# USB_Hub.net
KiCad netlist of a schematic drawn in Altium Designer
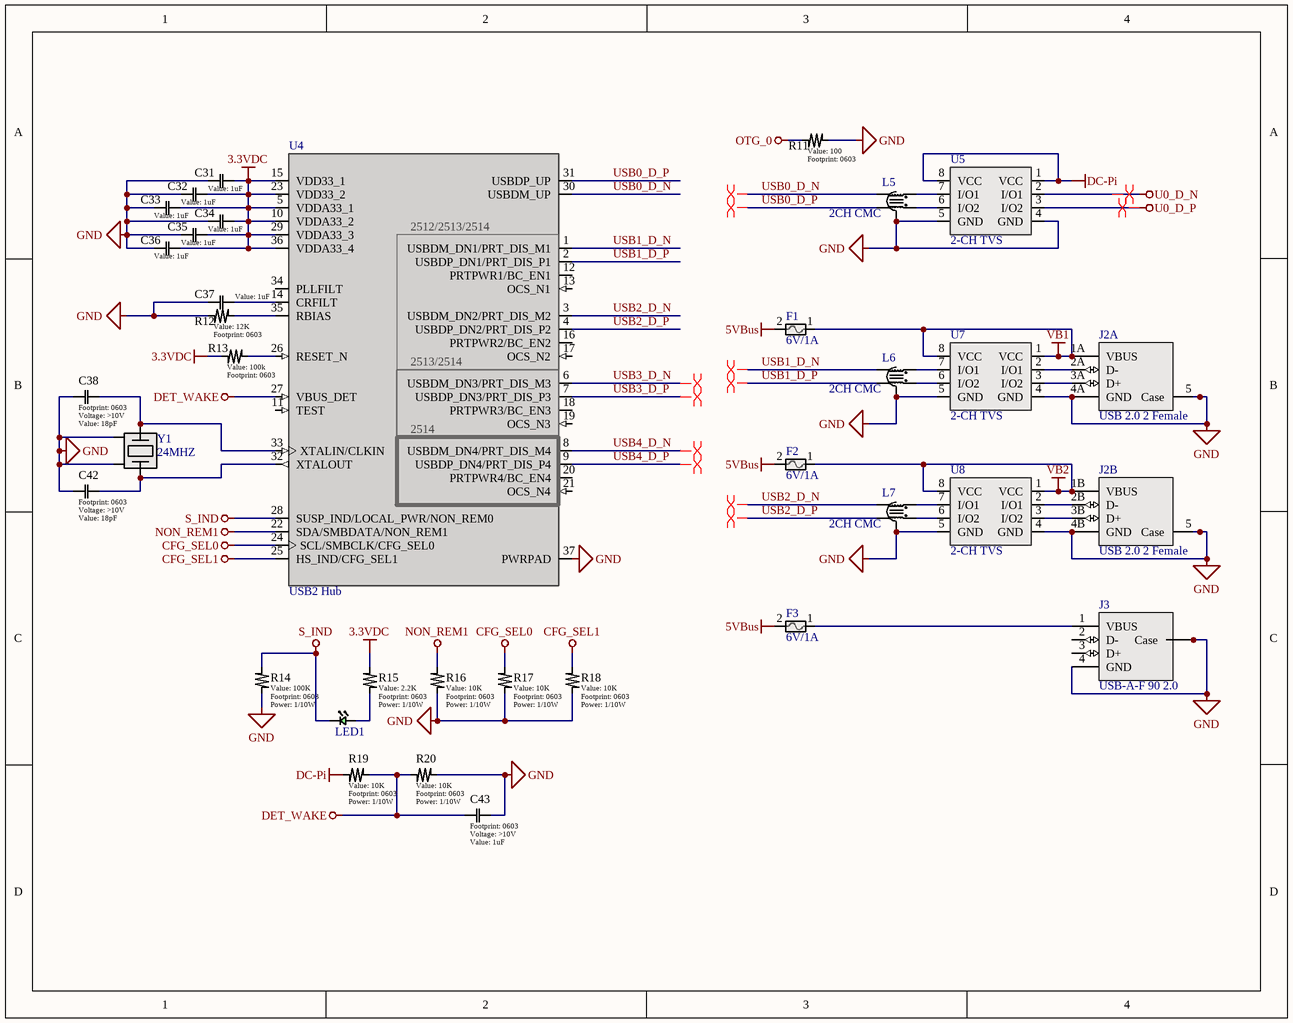
[diagram p0: USB Hub.SchDoc]

(export (version "E")
  (design (tool "Eeschema 10.0.6"))
  (components
    (comp (ref "C31")
      (value "1uF")
      (footprint "0603")
      (fields
        (field (name "VOLTAGE") ">10V")
        (field (name "TOLERANCE") "10%")
        (field (name "Comment") "Generic Capacitor")
      )
      (libsource (lib "Capacitors") (part "Generic Capacitor"))
    )
    (comp (ref "C32")
      (value "1uF")
      (footprint "0603")
      (fields
        (field (name "VOLTAGE") ">10V")
        (field (name "TOLERANCE") "10%")
        (field (name "Comment") "Generic Capacitor")
      )
      (libsource (lib "Capacitors") (part "Generic Capacitor"))
    )
    (comp (ref "C33")
      (value "1uF")
      (footprint "0603")
      (fields
        (field (name "VOLTAGE") ">10V")
        (field (name "TOLERANCE") "10%")
        (field (name "Comment") "Generic Capacitor")
      )
      (libsource (lib "Capacitors") (part "Generic Capacitor"))
    )
    (comp (ref "C34")
      (value "1uF")
      (footprint "0603")
      (fields
        (field (name "VOLTAGE") ">10V")
        (field (name "TOLERANCE") "10%")
        (field (name "Comment") "Generic Capacitor")
      )
      (libsource (lib "Capacitors") (part "Generic Capacitor"))
    )
    (comp (ref "C35")
      (value "1uF")
      (footprint "0603")
      (fields
        (field (name "VOLTAGE") ">10V")
        (field (name "TOLERANCE") "10%")
        (field (name "Comment") "Generic Capacitor")
      )
      (libsource (lib "Capacitors") (part "Generic Capacitor"))
    )
    (comp (ref "C36")
      (value "1uF")
      (footprint "0603")
      (fields
        (field (name "VOLTAGE") ">10V")
        (field (name "TOLERANCE") "10%")
        (field (name "Comment") "Generic Capacitor")
      )
      (libsource (lib "Capacitors") (part "Generic Capacitor"))
    )
    (comp (ref "C37")
      (value "1uF")
      (footprint "0603")
      (fields
        (field (name "VOLTAGE") ">10V")
        (field (name "TOLERANCE") "10%")
        (field (name "Comment") "Generic Capacitor")
      )
      (libsource (lib "Capacitors") (part "Generic Capacitor"))
    )
    (comp (ref "C38")
      (value "18pF")
      (footprint "0603")
      (fields
        (field (name "VOLTAGE") ">10V")
        (field (name "TOLERANCE") "10%")
        (field (name "Comment") "Generic Capacitor")
      )
      (libsource (lib "Capacitors") (part "Generic Capacitor"))
    )
    (comp (ref "C42")
      (value "18pF")
      (footprint "0603")
      (fields
        (field (name "VOLTAGE") ">10V")
        (field (name "TOLERANCE") "10%")
        (field (name "Comment") "Generic Capacitor")
      )
      (libsource (lib "Capacitors") (part "Generic Capacitor"))
    )
    (comp (ref "C43")
      (value "1uF")
      (footprint "0603")
      (fields
        (field (name "VOLTAGE") ">10V")
        (field (name "TOLERANCE") "10%")
        (field (name "Comment") "Generic Capacitor")
      )
      (libsource (lib "Capacitors") (part "Generic Capacitor"))
    )
    (comp (ref "F1")
      (value "6V/1A")
      (footprint "0805")
      (description "Polymeric PTC Resettable Fuse 6V 1 A Ih Surface Mount 0805 (2012 Metric), Concave")
      (fields (field (name "MANUFACTURER") "Bel") (field (name "MANUFACTURER PART NUMBER") "0ZCK0100FF2E"))
      (libsource (lib "Regulators") (part "0ZCK0100FF2E"))
    )
    (comp (ref "F2")
      (value "6V/1A")
      (footprint "0805")
      (description "Polymeric PTC Resettable Fuse 6V 1 A Ih Surface Mount 0805 (2012 Metric), Concave")
      (fields (field (name "MANUFACTURER") "Bel") (field (name "MANUFACTURER PART NUMBER") "0ZCK0100FF2E"))
      (libsource (lib "Regulators") (part "0ZCK0100FF2E"))
    )
    (comp (ref "F3")
      (value "6V/1A")
      (footprint "0805")
      (description "Polymeric PTC Resettable Fuse 6V 1 A Ih Surface Mount 0805 (2012 Metric), Concave")
      (fields (field (name "MANUFACTURER") "Bel") (field (name "MANUFACTURER PART NUMBER") "0ZCK0100FF2E"))
      (libsource (lib "Regulators") (part "0ZCK0100FF2E"))
    )
    (comp (ref "J2")
      (value "USB 2.0 2 Female")
      (footprint "907-111A1022D10200")
      (description "USB 2.0 2 8 Female Type-A Plugin USB Connectors ROHS")
      (libsource (lib "Connectors") (part "907-111A1022D10200"))
    )
    (comp (ref "J3")
      (value "USB-A-F 90 2.0")
      (footprint "Molex_67329-8000")
      (description "USB 2.0 1 Side insertion 4P Female Type-A Plugin")
      (libsource (lib "Connectors") (part "673298000"))
    )
    (comp (ref "L5")
      (value "2CH CMC")
      (footprint "SMD-6-2CH")
      (description "35Ω@100MHz -40℃~+85℃ 4Ω 5V 2 100mA SMD Common Mode Filters ROHS")
      (libsource (lib "Inductors") (part "ICMEF112P350MFR"))
    )
    (comp (ref "L6")
      (value "2CH CMC")
      (footprint "SMD-6-2CH")
      (description "35Ω@100MHz -40℃~+85℃ 4Ω 5V 2 100mA SMD Common Mode Filters ROHS")
      (libsource (lib "Inductors") (part "ICMEF112P350MFR"))
    )
    (comp (ref "L7")
      (value "2CH CMC")
      (footprint "SMD-6-2CH")
      (description "35Ω@100MHz -40℃~+85℃ 4Ω 5V 2 100mA SMD Common Mode Filters ROHS")
      (libsource (lib "Inductors") (part "ICMEF112P350MFR"))
    )
    (comp (ref "LED1")
      (value "LTST-C191KGKT")
      (footprint "0603 (1608 Metric) Concave")
      (description "LED Uni-Color Green 574nm 2-Pin Chip LED T/R")
      (libsource (lib "Gamber - Johnson LLC") (part "LTST-C191KGKT"))
    )
    (comp (ref "R11")
      (value "100")
      (footprint "0603")
      (fields
        (field (name "TOLERANCE") "1%")
        (field (name "POWER") "1/10W")
        (field (name "Comment") "Generic Resistor")
      )
      (libsource (lib "Resistors") (part "Generic Resistor"))
    )
    (comp (ref "R12")
      (value "12K")
      (footprint "0603")
      (fields
        (field (name "TOLERANCE") "1%")
        (field (name "POWER") "1/10W")
        (field (name "Comment") "Generic Resistor")
      )
      (libsource (lib "Resistors") (part "Generic Resistor"))
    )
    (comp (ref "R13")
      (value "100k")
      (footprint "0603")
      (fields
        (field (name "TOLERANCE") "1%")
        (field (name "POWER") "1/10W")
        (field (name "Comment") "Generic Resistor")
      )
      (libsource (lib "Resistors") (part "Generic Resistor"))
    )
    (comp (ref "R14")
      (value "100K")
      (footprint "0603")
      (fields
        (field (name "TOLERANCE") "1%")
        (field (name "POWER") "1/10W")
        (field (name "Comment") "Generic Resistor")
      )
      (libsource (lib "Resistors") (part "Generic Resistor"))
    )
    (comp (ref "R15")
      (value "2.2K")
      (footprint "0603")
      (fields
        (field (name "TOLERANCE") "1%")
        (field (name "POWER") "1/10W")
        (field (name "Comment") "Generic Resistor")
      )
      (libsource (lib "Resistors") (part "Generic Resistor"))
    )
    (comp (ref "R16")
      (value "10K")
      (footprint "0603")
      (fields
        (field (name "TOLERANCE") "1%")
        (field (name "POWER") "1/10W")
        (field (name "Comment") "Generic Resistor")
      )
      (libsource (lib "Resistors") (part "Generic Resistor"))
    )
    (comp (ref "R17")
      (value "10K")
      (footprint "0603")
      (fields
        (field (name "TOLERANCE") "1%")
        (field (name "POWER") "1/10W")
        (field (name "Comment") "Generic Resistor")
      )
      (libsource (lib "Resistors") (part "Generic Resistor"))
    )
    (comp (ref "R18")
      (value "10K")
      (footprint "0603")
      (fields
        (field (name "TOLERANCE") "1%")
        (field (name "POWER") "1/10W")
        (field (name "Comment") "Generic Resistor")
      )
      (libsource (lib "Resistors") (part "Generic Resistor"))
    )
    (comp (ref "R19")
      (value "10K")
      (footprint "0603")
      (fields
        (field (name "TOLERANCE") "1%")
        (field (name "POWER") "1/10W")
        (field (name "Comment") "Generic Resistor")
      )
      (libsource (lib "Resistors") (part "Generic Resistor"))
    )
    (comp (ref "R20")
      (value "10K")
      (footprint "0603")
      (fields
        (field (name "TOLERANCE") "1%")
        (field (name "POWER") "1/10W")
        (field (name "Comment") "Generic Resistor")
      )
      (libsource (lib "Resistors") (part "Generic Resistor"))
    )
    (comp (ref "U4")
      (value "USB2 Hub")
      (footprint "36-QFN (6x6)")
      (description "USB Hub Controller USB 2.0 USB Interface 36-QFN _6x6_")
      (fields (field (name "MF") "Microchip") (field (name "DIGI-KEY_PART_NUMBER") "USB2514BI-AEZG-ND"))
      (libsource (lib "Hub ICs") (part "USB251xBI-AEZG"))
    )
    (comp (ref "U5")
      (value "2-CH TVS")
      (footprint "8-SOIC")
      (description "TVS DIODE 5.25VWM 8-SOIC")
      (libsource (lib "Diodes") (part "USB6B1RL"))
    )
    (comp (ref "U7")
      (value "2-CH TVS")
      (footprint "8-SOIC")
      (description "TVS DIODE 5.25VWM 8-SOIC")
      (libsource (lib "Diodes") (part "USB6B1RL"))
    )
    (comp (ref "U8")
      (value "2-CH TVS")
      (footprint "8-SOIC")
      (description "TVS DIODE 5.25VWM 8-SOIC")
      (libsource (lib "Diodes") (part "USB6B1RL"))
    )
    (comp (ref "Y1")
      (value "24MHZ")
      (footprint "SMD2520-4P")
      (description "24MHz 20pF ±10ppm ±30ppm SMD-2520-4P Crystals ROHS")
      (libsource (lib "Misc ICs") (part "CM4024M00020001"))
    )
  )
  (nets
    (net (code "1") (name "/USB0_D_N") (class "Default")
      (node (ref "L5") (pin "4") (pinfunction "4_4") (pintype "passive"))
      (node (ref "U4") (pin "30") (pinfunction "USBDM_UP_30") (pintype "bidirectional"))
    )
    (net (code "2") (name "/USB0_D_P") (class "Default")
      (node (ref "L5") (pin "3") (pinfunction "3_3") (pintype "passive"))
      (node (ref "U4") (pin "31") (pinfunction "USBDP_UP_31") (pintype "bidirectional"))
    )
    (net (code "3") (name "/USB1_D_N") (class "Default")
      (node (ref "L6") (pin "4") (pinfunction "4_4") (pintype "passive"))
      (node (ref "U4") (pin "1") (pinfunction "USBDM_DN1/PRT_DIS_M1_1") (pintype "bidirectional"))
    )
    (net (code "4") (name "/USB1_D_P") (class "Default")
      (node (ref "L6") (pin "3") (pinfunction "3_3") (pintype "passive"))
      (node (ref "U4") (pin "2") (pinfunction "USBDP_DN1/PRT_DIS_P1_2") (pintype "bidirectional"))
    )
    (net (code "5") (name "/USB2_D_N") (class "Default")
      (node (ref "L7") (pin "4") (pinfunction "4_4") (pintype "passive"))
      (node (ref "U4") (pin "3") (pinfunction "USBDM_DN2/PRT_DIS_M2_3") (pintype "bidirectional"))
    )
    (net (code "6") (name "/USB2_D_P") (class "Default")
      (node (ref "L7") (pin "3") (pinfunction "3_3") (pintype "passive"))
      (node (ref "U4") (pin "4") (pinfunction "USBDP_DN2/PRT_DIS_P2_4") (pintype "bidirectional"))
    )
    (net (code "7") (name "/USB3_D_N") (class "Default")
      (node (ref "U4") (pin "6") (pinfunction "USBDM_DN3/PRT_DIS_M3_6") (pintype "bidirectional"))
    )
    (net (code "8") (name "/USB3_D_P") (class "Default")
      (node (ref "U4") (pin "7") (pinfunction "USBDP_DN3/PRT_DIS_P3_7") (pintype "bidirectional"))
    )
    (net (code "9") (name "/USB4_D_N") (class "Default")
      (node (ref "U4") (pin "8") (pinfunction "USBDM_DN4/PRT_DIS_M4_8") (pintype "bidirectional"))
    )
    (net (code "10") (name "/USB4_D_P") (class "Default")
      (node (ref "U4") (pin "9") (pinfunction "USBDP_DN4/PRT_DIS_P4_9") (pintype "bidirectional"))
    )
    (net (code "11") (name "3.3VDC") (class "Default")
      (node (ref "C31") (pin "2") (pinfunction "2_2") (pintype "passive"))
      (node (ref "C32") (pin "2") (pinfunction "2_2") (pintype "passive"))
      (node (ref "C33") (pin "2") (pinfunction "2_2") (pintype "passive"))
      (node (ref "C34") (pin "2") (pinfunction "2_2") (pintype "passive"))
      (node (ref "C35") (pin "2") (pinfunction "2_2") (pintype "passive"))
      (node (ref "C36") (pin "2") (pinfunction "2_2") (pintype "passive"))
      (node (ref "R13") (pin "1") (pinfunction "1_1") (pintype "passive"))
      (node (ref "R15") (pin "1") (pinfunction "1_1") (pintype "passive"))
      (node (ref "U4") (pin "10") (pinfunction "VDDA33_2_10") (pintype "power_in"))
      (node (ref "U4") (pin "15") (pinfunction "VDD33_1_15") (pintype "power_in"))
      (node (ref "U4") (pin "23") (pinfunction "VDD33_2_23") (pintype "power_in"))
      (node (ref "U4") (pin "29") (pinfunction "VDDA33_3_29") (pintype "power_in"))
      (node (ref "U4") (pin "36") (pinfunction "VDDA33_4_36") (pintype "power_in"))
      (node (ref "U4") (pin "5") (pinfunction "VDDA33_1_5") (pintype "power_in"))
    )
    (net (code "12") (name "5VBus") (class "Default")
      (node (ref "F1") (pin "2") (pinfunction "2_2") (pintype "passive"))
      (node (ref "F2") (pin "2") (pinfunction "2_2") (pintype "passive"))
      (node (ref "F3") (pin "2") (pinfunction "2_2") (pintype "passive"))
    )
    (net (code "13") (name "CFG_SEL0") (class "Default")
      (node (ref "R17") (pin "1") (pinfunction "1_1") (pintype "passive"))
      (node (ref "U4") (pin "24") (pinfunction "SCL/SMBCLK/CFG_SEL0_24") (pintype "bidirectional"))
    )
    (net (code "14") (name "CFG_SEL1") (class "Default")
      (node (ref "R18") (pin "1") (pinfunction "1_1") (pintype "passive"))
      (node (ref "U4") (pin "25") (pinfunction "HS_IND/CFG_SEL1_25") (pintype "bidirectional"))
    )
    (net (code "15") (name "DC-Pi") (class "Default")
      (node (ref "R19") (pin "1") (pinfunction "1_1") (pintype "passive"))
      (node (ref "U5") (pin "1") (pinfunction "VCC_1") (pintype "power_in"))
      (node (ref "U5") (pin "8") (pinfunction "VCC_8") (pintype "power_in"))
    )
    (net (code "16") (name "DET_WAKE") (class "Default")
      (node (ref "C43") (pin "1") (pinfunction "1_1") (pintype "passive"))
      (node (ref "R19") (pin "2") (pinfunction "2_2") (pintype "passive"))
      (node (ref "R20") (pin "1") (pinfunction "1_1") (pintype "passive"))
      (node (ref "U4") (pin "27") (pinfunction "VBUS_DET_27") (pintype "input"))
    )
    (net (code "17") (name "GND") (class "Default")
      (node (ref "C31") (pin "1") (pinfunction "1_1") (pintype "passive"))
      (node (ref "C32") (pin "1") (pinfunction "1_1") (pintype "passive"))
      (node (ref "C33") (pin "1") (pinfunction "1_1") (pintype "passive"))
      (node (ref "C34") (pin "1") (pinfunction "1_1") (pintype "passive"))
      (node (ref "C35") (pin "1") (pinfunction "1_1") (pintype "passive"))
      (node (ref "C36") (pin "1") (pinfunction "1_1") (pintype "passive"))
      (node (ref "C37") (pin "1") (pinfunction "1_1") (pintype "passive"))
      (node (ref "C38") (pin "1") (pinfunction "1_1") (pintype "passive"))
      (node (ref "C42") (pin "1") (pinfunction "1_1") (pintype "passive"))
      (node (ref "C43") (pin "2") (pinfunction "2_2") (pintype "passive"))
      (node (ref "J2") (pin "4A") (pinfunction "GND_4A") (pintype "power_in"))
      (node (ref "J2") (pin "4B") (pinfunction "GND_4B") (pintype "power_in"))
      (node (ref "J2") (pin "5") (pinfunction "Case_5") (pintype "passive"))
      (node (ref "J3") (pin "4") (pinfunction "GND_4") (pintype "power_in"))
      (node (ref "J3") (pin "5") (pinfunction "Case_5") (pintype "passive"))
      (node (ref "J3") (pin "6") (pinfunction "Case_6") (pintype "passive"))
      (node (ref "J3") (pin "7") (pinfunction "Case_7") (pintype "passive"))
      (node (ref "J3") (pin "8") (pinfunction "Case_8") (pintype "passive"))
      (node (ref "L5") (pin "5") (pinfunction "5_5") (pintype "passive"))
      (node (ref "L5") (pin "6") (pinfunction "6_6") (pintype "passive"))
      (node (ref "L6") (pin "5") (pinfunction "5_5") (pintype "passive"))
      (node (ref "L6") (pin "6") (pinfunction "6_6") (pintype "passive"))
      (node (ref "L7") (pin "5") (pinfunction "5_5") (pintype "passive"))
      (node (ref "L7") (pin "6") (pinfunction "6_6") (pintype "passive"))
      (node (ref "R11") (pin "2") (pinfunction "2_2") (pintype "passive"))
      (node (ref "R12") (pin "1") (pinfunction "1_1") (pintype "passive"))
      (node (ref "R14") (pin "2") (pinfunction "2_2") (pintype "passive"))
      (node (ref "R16") (pin "2") (pinfunction "2_2") (pintype "passive"))
      (node (ref "R17") (pin "2") (pinfunction "2_2") (pintype "passive"))
      (node (ref "R18") (pin "2") (pinfunction "2_2") (pintype "passive"))
      (node (ref "R20") (pin "2") (pinfunction "2_2") (pintype "passive"))
      (node (ref "U4") (pin "37") (pinfunction "PWRPAD_37") (pintype "power_in"))
      (node (ref "U5") (pin "4") (pinfunction "GND_4") (pintype "power_in"))
      (node (ref "U5") (pin "5") (pinfunction "GND_5") (pintype "power_in"))
      (node (ref "U7") (pin "4") (pinfunction "GND_4") (pintype "power_in"))
      (node (ref "U7") (pin "5") (pinfunction "GND_5") (pintype "power_in"))
      (node (ref "U8") (pin "4") (pinfunction "GND_4") (pintype "power_in"))
      (node (ref "U8") (pin "5") (pinfunction "GND_5") (pintype "power_in"))
      (node (ref "Y1") (pin "2") (pinfunction "GND_2") (pintype "power_in"))
      (node (ref "Y1") (pin "4") (pinfunction "GND_4") (pintype "power_in"))
    )
    (net (code "18") (name "NON_REM1") (class "Default")
      (node (ref "R16") (pin "1") (pinfunction "1_1") (pintype "passive"))
      (node (ref "U4") (pin "22") (pinfunction "SDA/SMBDATA/NON_REM1_22") (pintype "bidirectional"))
    )
    (net (code "19") (name "Net-(J2A-D+)") (class "Default")
      (node (ref "J2") (pin "3A") (pinfunction "D+_3A") (pintype "bidirectional"))
      (node (ref "U7") (pin "3") (pinfunction "I/O2_3") (pintype "bidirectional"))
    )
    (net (code "20") (name "Net-(J2A-D-)") (class "Default")
      (node (ref "J2") (pin "2A") (pinfunction "D-_2A") (pintype "bidirectional"))
      (node (ref "U7") (pin "2") (pinfunction "I/O1_2") (pintype "bidirectional"))
    )
    (net (code "21") (name "Net-(J2B-D+)") (class "Default")
      (node (ref "J2") (pin "3B") (pinfunction "D+_3B") (pintype "bidirectional"))
      (node (ref "U8") (pin "3") (pinfunction "I/O2_3") (pintype "bidirectional"))
    )
    (net (code "22") (name "Net-(J2B-D-)") (class "Default")
      (node (ref "J2") (pin "2B") (pinfunction "D-_2B") (pintype "bidirectional"))
      (node (ref "U8") (pin "2") (pinfunction "I/O1_2") (pintype "bidirectional"))
    )
    (net (code "23") (name "Net-(J3-VBUS)") (class "Default")
      (node (ref "F3") (pin "1") (pinfunction "1_1") (pintype "passive"))
      (node (ref "J3") (pin "1") (pinfunction "VBUS_1") (pintype "power_in"))
    )
    (net (code "24") (name "Net-(L5-Pad1)") (class "Default")
      (node (ref "L5") (pin "1") (pinfunction "1_1") (pintype "passive"))
      (node (ref "U5") (pin "7") (pinfunction "I/O1_7") (pintype "bidirectional"))
    )
    (net (code "25") (name "Net-(L5-Pad2)") (class "Default")
      (node (ref "L5") (pin "2") (pinfunction "2_2") (pintype "passive"))
      (node (ref "U5") (pin "6") (pinfunction "I/O2_6") (pintype "bidirectional"))
    )
    (net (code "26") (name "Net-(L6-Pad1)") (class "Default")
      (node (ref "L6") (pin "1") (pinfunction "1_1") (pintype "passive"))
      (node (ref "U7") (pin "7") (pinfunction "I/O1_7") (pintype "bidirectional"))
    )
    (net (code "27") (name "Net-(L6-Pad2)") (class "Default")
      (node (ref "L6") (pin "2") (pinfunction "2_2") (pintype "passive"))
      (node (ref "U7") (pin "6") (pinfunction "I/O2_6") (pintype "bidirectional"))
    )
    (net (code "28") (name "Net-(L7-Pad1)") (class "Default")
      (node (ref "L7") (pin "1") (pinfunction "1_1") (pintype "passive"))
      (node (ref "U8") (pin "7") (pinfunction "I/O1_7") (pintype "bidirectional"))
    )
    (net (code "29") (name "Net-(L7-Pad2)") (class "Default")
      (node (ref "L7") (pin "2") (pinfunction "2_2") (pintype "passive"))
      (node (ref "U8") (pin "6") (pinfunction "I/O2_6") (pintype "bidirectional"))
    )
    (net (code "30") (name "Net-(LED1-Anode)") (class "Default")
      (node (ref "LED1") (pin "2") (pinfunction "Anode_2") (pintype "passive"))
      (node (ref "R15") (pin "2") (pinfunction "2_2") (pintype "passive"))
    )
    (net (code "31") (name "Net-(U4-CRFILT)") (class "Default")
      (node (ref "C37") (pin "2") (pinfunction "2_2") (pintype "passive"))
      (node (ref "U4") (pin "14") (pinfunction "CRFILT_14") (pintype "passive"))
    )
    (net (code "32") (name "Net-(U4-RBIAS)") (class "Default")
      (node (ref "R12") (pin "2") (pinfunction "2_2") (pintype "passive"))
      (node (ref "U4") (pin "35") (pinfunction "RBIAS_35") (pintype "passive"))
    )
    (net (code "33") (name "Net-(U4-RESET_N)") (class "Default")
      (node (ref "R13") (pin "2") (pinfunction "2_2") (pintype "passive"))
      (node (ref "U4") (pin "26") (pinfunction "RESET_N_26") (pintype "input"))
    )
    (net (code "34") (name "Net-(U4-XTALIN{slash}CLKIN)") (class "Default")
      (node (ref "C38") (pin "2") (pinfunction "2_2") (pintype "passive"))
      (node (ref "U4") (pin "33") (pinfunction "XTALIN/CLKIN_33") (pintype "input"))
      (node (ref "Y1") (pin "1") (pintype "passive"))
    )
    (net (code "35") (name "Net-(U4-XTALOUT)") (class "Default")
      (node (ref "C42") (pin "2") (pinfunction "2_2") (pintype "passive"))
      (node (ref "U4") (pin "32") (pinfunction "XTALOUT_32") (pintype "output"))
      (node (ref "Y1") (pin "3") (pintype "passive"))
    )
    (net (code "36") (name "OTG_0") (class "Default")
      (node (ref "R11") (pin "1") (pinfunction "1_1") (pintype "passive"))
    )
    (net (code "37") (name "S_IND") (class "Default")
      (node (ref "LED1") (pin "1") (pinfunction "Cathode_1") (pintype "passive"))
      (node (ref "R14") (pin "1") (pinfunction "1_1") (pintype "passive"))
      (node (ref "U4") (pin "28") (pinfunction "SUSP_IND/LOCAL_PWR/NON_REM0_28") (pintype "bidirectional"))
    )
    (net (code "38") (name "U0_D_N") (class "Default")
      (node (ref "U5") (pin "2") (pinfunction "I/O1_2") (pintype "bidirectional"))
    )
    (net (code "39") (name "U0_D_P") (class "Default")
      (node (ref "U5") (pin "3") (pinfunction "I/O2_3") (pintype "bidirectional"))
    )
    (net (code "40") (name "VB1") (class "Default")
      (node (ref "F1") (pin "1") (pinfunction "1_1") (pintype "passive"))
      (node (ref "J2") (pin "1A") (pinfunction "VBUS_1A") (pintype "power_in"))
      (node (ref "U7") (pin "1") (pinfunction "VCC_1") (pintype "power_in"))
      (node (ref "U7") (pin "8") (pinfunction "VCC_8") (pintype "power_in"))
    )
    (net (code "41") (name "VB2") (class "Default")
      (node (ref "F2") (pin "1") (pinfunction "1_1") (pintype "passive"))
      (node (ref "J2") (pin "1B") (pinfunction "VBUS_1B") (pintype "power_in"))
      (node (ref "U8") (pin "1") (pinfunction "VCC_1") (pintype "power_in"))
      (node (ref "U8") (pin "8") (pinfunction "VCC_8") (pintype "power_in"))
    )
    (net (code "42") (name "unconnected-(J3-D+-Pad3)") (class "Default")
      (node (ref "J3") (pin "3") (pinfunction "D+_3") (pintype "bidirectional"))
    )
    (net (code "43") (name "unconnected-(J3-D--Pad2)") (class "Default")
      (node (ref "J3") (pin "2") (pinfunction "D-_2") (pintype "bidirectional"))
    )
    (net (code "44") (name "unconnected-(U4-OCS_N1-Pad13)") (class "Default")
      (node (ref "U4") (pin "13") (pinfunction "OCS_N1_13") (pintype "input"))
    )
    (net (code "45") (name "unconnected-(U4-OCS_N2-Pad17)") (class "Default")
      (node (ref "U4") (pin "17") (pinfunction "OCS_N2_17") (pintype "input"))
    )
    (net (code "46") (name "unconnected-(U4-OCS_N3-Pad19)") (class "Default")
      (node (ref "U4") (pin "19") (pinfunction "OCS_N3_19") (pintype "input"))
    )
    (net (code "47") (name "unconnected-(U4-OCS_N4-Pad21)") (class "Default")
      (node (ref "U4") (pin "21") (pinfunction "OCS_N4_21") (pintype "input"))
    )
    (net (code "48") (name "unconnected-(U4-PLLFILT-Pad34)") (class "Default")
      (node (ref "U4") (pin "34") (pinfunction "PLLFILT_34") (pintype "passive"))
    )
    (net (code "49") (name "unconnected-(U4-PRTPWR1{slash}BC_EN1-Pad12)") (class "Default")
      (node (ref "U4") (pin "12") (pinfunction "PRTPWR1/BC_EN1_12") (pintype "bidirectional"))
    )
    (net (code "50") (name "unconnected-(U4-PRTPWR2{slash}BC_EN2-Pad16)") (class "Default")
      (node (ref "U4") (pin "16") (pinfunction "PRTPWR2/BC_EN2_16") (pintype "bidirectional"))
    )
    (net (code "51") (name "unconnected-(U4-PRTPWR3{slash}BC_EN3-Pad18)") (class "Default")
      (node (ref "U4") (pin "18") (pinfunction "PRTPWR3/BC_EN3_18") (pintype "bidirectional"))
    )
    (net (code "52") (name "unconnected-(U4-PRTPWR4{slash}BC_EN4-Pad20)") (class "Default")
      (node (ref "U4") (pin "20") (pinfunction "PRTPWR4/BC_EN4_20") (pintype "bidirectional"))
    )
    (net (code "53") (name "unconnected-(U4-TEST-Pad11)") (class "Default")
      (node (ref "U4") (pin "11") (pinfunction "TEST_11") (pintype "input"))
    )
  )
)
